# OSO-MISC-22-003_Ring_Thing.net
KiCad netlist of a schematic drawn in EAGLE
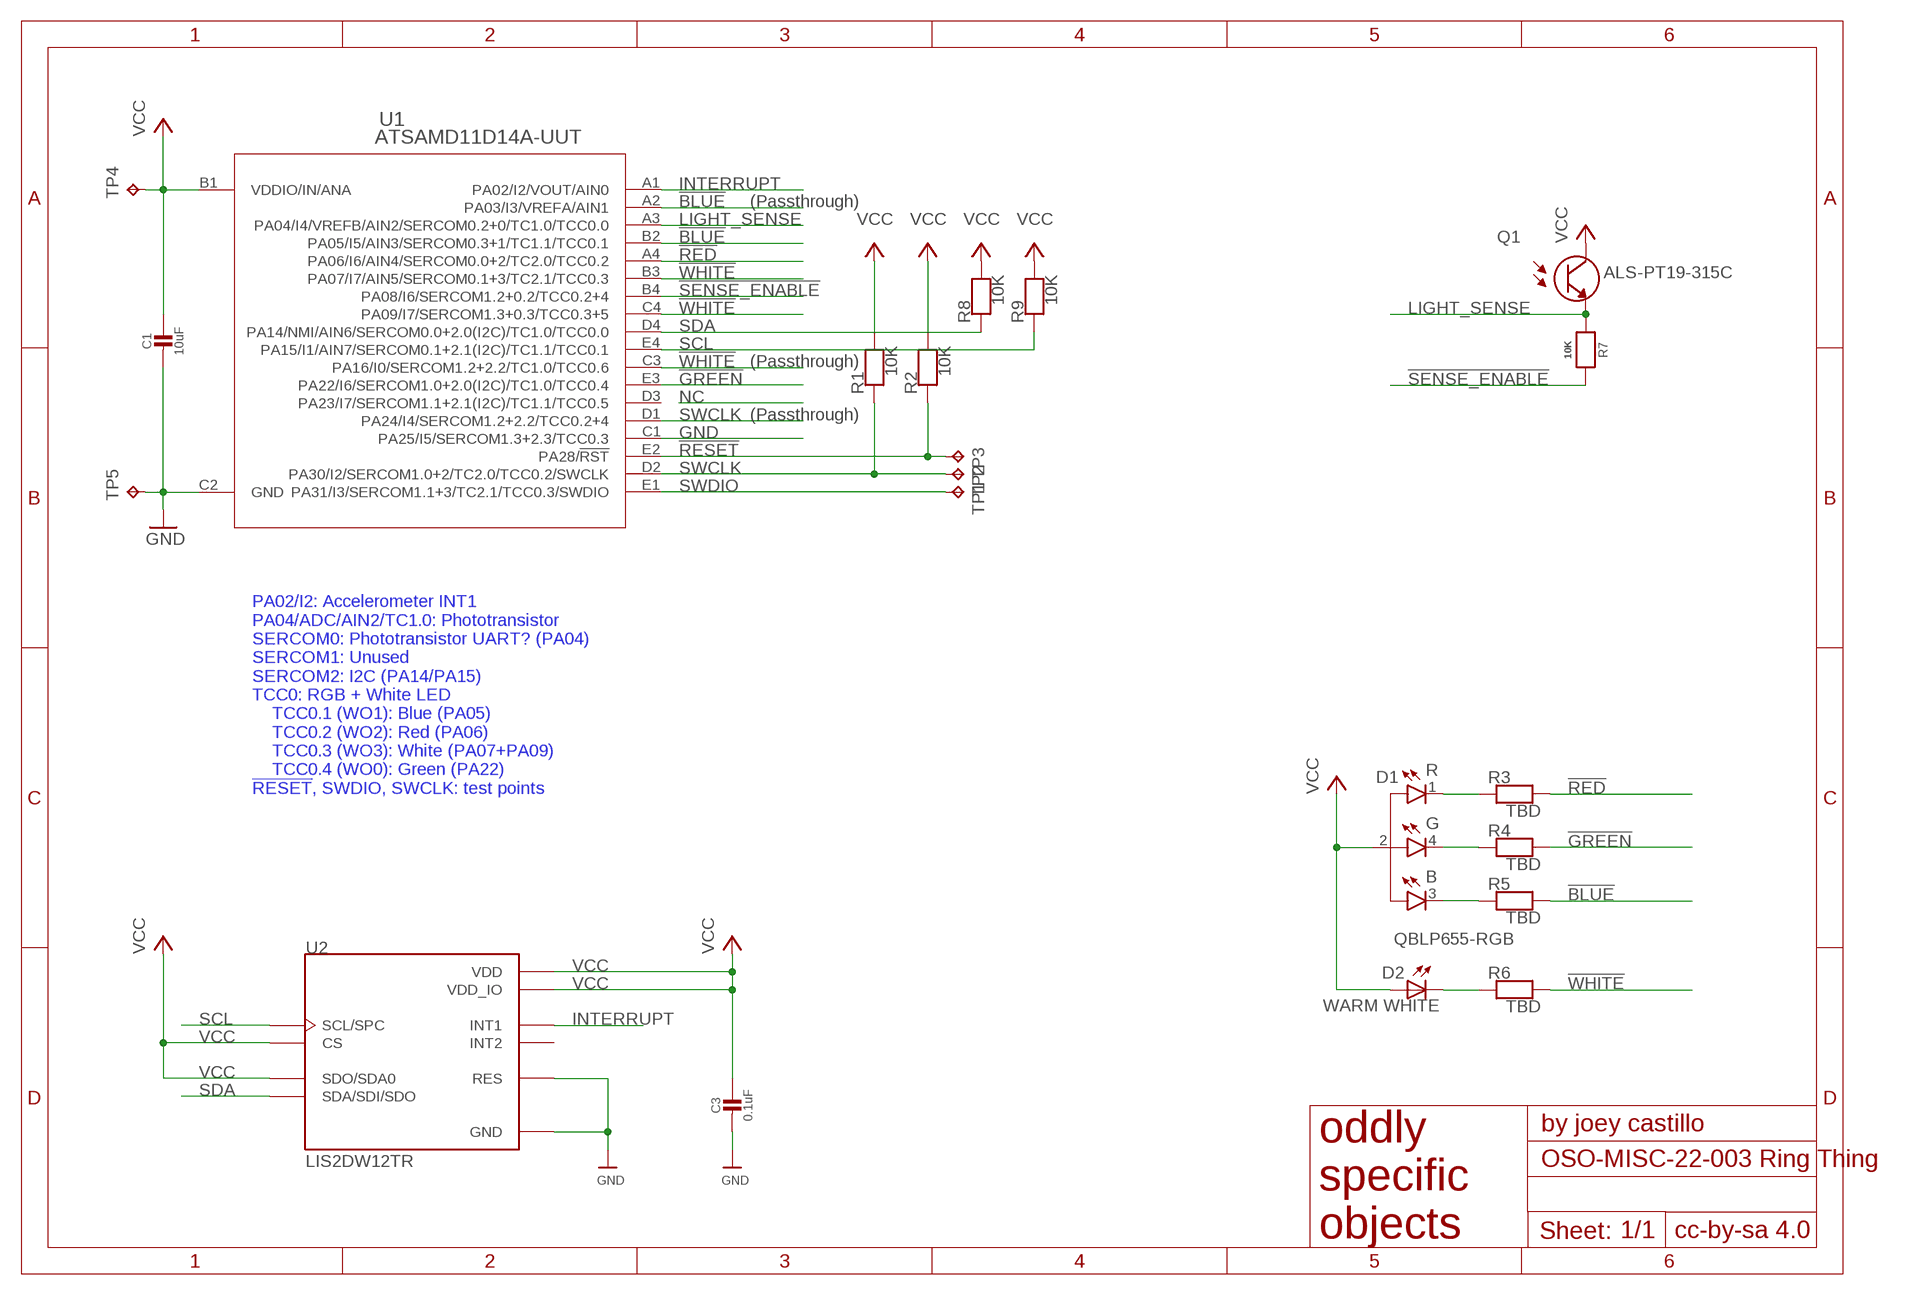
[diagram p0: schematic, sheet 1]

(export (version "E")
  (design (tool "Eeschema 10.0.6"))
  (components
    (comp (ref "C1")
      (value "10uF")
      (footprint "eagle-import:_0603MP")
      (libsource (lib "eagle-import") (part "CAP_CERAMIC_0603MP"))
    )
    (comp (ref "C3")
      (value "0.1uF")
      (footprint "eagle-import:_0402MP")
      (libsource (lib "eagle-import") (part "CAP_CERAMIC_0402MP"))
    )
    (comp (ref "D1")
      (value "QBLP655-RGB")
      (footprint "eagle-import:LED_QBLP655")
      (fields
        (field (name "DIGI-KEY_PART_NUMBER") "160-2026-1-ND")
        (field (name "MF") "Lite-On Inc.")
        (field (name "MP") "LTST-C235KGKRKT")
      )
      (libsource (lib "eagle-import") (part "QBLP655-RGB"))
    )
    (comp (ref "D2")
      (value "WARM WHITE")
      (footprint "eagle-import:CHIP-LED0603")
      (libsource (lib "eagle-import") (part "LEDCHIP-LED0603"))
    )
    (comp (ref "Q1")
      (value "ALS-PT19-315C")
      (footprint "eagle-import:XDCR_ALS-PT19-315C_L177_TR8")
      (fields
        (field (name "DIGI-KEY_PART_NUMBER") "1080-1244-2-ND")
        (field (name "MF") "Everlight")
        (field (name "MP") "ALS-PT19-315C/L177/TR8")
      )
      (libsource (lib "eagle-import") (part "ALS-PT19-315C/L177/TR8"))
    )
    (comp (ref "R1")
      (value "10K")
      (footprint "eagle-import:_0402MP")
      (libsource (lib "eagle-import") (part "RESISTOR_0402MP"))
    )
    (comp (ref "R2")
      (value "10K")
      (footprint "eagle-import:_0402MP")
      (libsource (lib "eagle-import") (part "RESISTOR_0402MP"))
    )
    (comp (ref "R3")
      (value "TBD")
      (footprint "eagle-import:_0402MP")
      (libsource (lib "eagle-import") (part "RESISTOR_0402MP"))
    )
    (comp (ref "R4")
      (value "TBD")
      (footprint "eagle-import:_0402MP")
      (libsource (lib "eagle-import") (part "RESISTOR_0402MP"))
    )
    (comp (ref "R5")
      (value "TBD")
      (footprint "eagle-import:_0402MP")
      (libsource (lib "eagle-import") (part "RESISTOR_0402MP"))
    )
    (comp (ref "R6")
      (value "TBD")
      (footprint "eagle-import:_0402MP")
      (libsource (lib "eagle-import") (part "RESISTOR_0402MP"))
    )
    (comp (ref "R7")
      (value "10K")
      (footprint "eagle-import:_0402MP")
      (libsource (lib "eagle-import") (part "RESISTOR_0402MP"))
    )
    (comp (ref "R8")
      (value "10K")
      (footprint "eagle-import:_0402MP")
      (libsource (lib "eagle-import") (part "RESISTOR_0402MP"))
    )
    (comp (ref "R9")
      (value "10K")
      (footprint "eagle-import:_0402MP")
      (libsource (lib "eagle-import") (part "RESISTOR_0402MP"))
    )
    (comp (ref "TP1")
      (value "TPTP10R")
      (footprint "eagle-import:TP10R")
      (libsource (lib "eagle-import") (part "TPTP10R"))
    )
    (comp (ref "TP2")
      (value "TPTP10R")
      (footprint "eagle-import:TP10R")
      (libsource (lib "eagle-import") (part "TPTP10R"))
    )
    (comp (ref "TP3")
      (value "TPTP10R")
      (footprint "eagle-import:TP10R")
      (libsource (lib "eagle-import") (part "TPTP10R"))
    )
    (comp (ref "TP4")
      (value "TPTP12SQ")
      (footprint "eagle-import:TP12SQ")
      (libsource (lib "eagle-import") (part "TPTP12SQ"))
    )
    (comp (ref "TP5")
      (value "TPTP20R")
      (footprint "eagle-import:TP20R")
      (libsource (lib "eagle-import") (part "TPTP20R"))
    )
    (comp (ref "U1")
      (value "ATSAMD11D14A-UUT")
      (footprint "eagle-import:WLCSP20_2P4X1P9_MCH")
      (fields (field (name "COPYRIGHT") "Copyright (C) 2022 Ultra Librarian. All rights reserved."))
      (libsource (lib "eagle-import") (part "ATSAMD11D14A-UUT"))
    )
    (comp (ref "U2")
      (value "LIS2DW12TR")
      (footprint "eagle-import:LGA12R50P4X4_200X200X70")
      (fields (field (name "MF") "STMicroelectronics"))
      (libsource (lib "eagle-import") (part "LIS2DW12TR"))
    )
  )
  (nets
    (net (code "1") (name "/INTERRUPT") (class "Default")
      (node (ref "U1") (pin "A1") (pinfunction "PA02/I2/VOUT/AIN0_A1") (pintype "bidirectional"))
      (node (ref "U2") (pin "12") (pinfunction "INT1_12") (pintype "output"))
    )
    (net (code "2") (name "/LIGHT_SENSE") (class "Default")
      (node (ref "Q1") (pin "2") (pinfunction "E_2") (pintype "passive"))
      (node (ref "R7") (pin "1") (pinfunction "1_1") (pintype "passive"))
      (node (ref "U1") (pin "A3") (pinfunction "PA04/I4/VREFB/AIN2/SERCOM0.2+0/TC1.0/TCC0.0_A3") (pintype "bidirectional"))
    )
    (net (code "4") (name "/SCL") (class "Default")
      (node (ref "R9") (pin "1") (pinfunction "1_1") (pintype "passive"))
      (node (ref "U1") (pin "E4") (pinfunction "PA15/I1/AIN7/SERCOM0.1+2.1(I2C)/TC1.1/TCC0.1_E4") (pintype "bidirectional"))
      (node (ref "U2") (pin "1") (pinfunction "SCL/SPC_1") (pintype "input"))
    )
    (net (code "5") (name "/SDA") (class "Default")
      (node (ref "R8") (pin "1") (pinfunction "1_1") (pintype "passive"))
      (node (ref "U1") (pin "D4") (pinfunction "PA14/NMI/AIN6/SERCOM0.0+2.0(I2C)/TC1.0/TCC0.0_D4") (pintype "bidirectional"))
      (node (ref "U2") (pin "4") (pinfunction "SDA/SDI/SDO_4") (pintype "bidirectional"))
    )
    (net (code "6") (name "/SWCLK") (class "Default")
      (node (ref "R1") (pin "1") (pinfunction "1_1") (pintype "passive"))
      (node (ref "TP2") (pin "TP") (pinfunction "TP_TP") (pintype "input"))
      (node (ref "U1") (pin "D1") (pinfunction "PA24/I4/SERCOM1.2+2.2/TCC0.2+4_D1") (pintype "bidirectional"))
      (node (ref "U1") (pin "D2") (pinfunction "PA30/I2/SERCOM1.0+2/TC2.0/TCC0.2/SWCLK_D2") (pintype "bidirectional"))
    )
    (net (code "7") (name "/SWDIO") (class "Default")
      (node (ref "TP1") (pin "TP") (pinfunction "TP_TP") (pintype "input"))
      (node (ref "U1") (pin "E1") (pinfunction "PA31/I3/SERCOM1.1+3/TC2.1/TCC0.3/SWDIO_E1") (pintype "bidirectional"))
    )
    (net (code "8") (name "/~{BLUE}") (class "Default")
      (node (ref "R5") (pin "2") (pinfunction "2_2") (pintype "passive"))
      (node (ref "U1") (pin "A2") (pinfunction "PA03/I3/VREFA/AIN1_A2") (pintype "bidirectional"))
      (node (ref "U1") (pin "B2") (pinfunction "PA05/I5/AIN3/SERCOM0.3+1/TC1.1/TCC0.1_B2") (pintype "bidirectional"))
    )
    (net (code "9") (name "/~{GREEN}") (class "Default")
      (node (ref "R4") (pin "2") (pinfunction "2_2") (pintype "passive"))
      (node (ref "U1") (pin "E3") (pinfunction "PA22/I6/SERCOM1.0+2.0(I2C)/TC1.0/TCC0.4_E3") (pintype "bidirectional"))
    )
    (net (code "10") (name "/~{RED}") (class "Default")
      (node (ref "R3") (pin "2") (pinfunction "2_2") (pintype "passive"))
      (node (ref "U1") (pin "A4") (pinfunction "PA06/I6/AIN4/SERCOM0.0+2/TC2.0/TCC0.2_A4") (pintype "bidirectional"))
    )
    (net (code "11") (name "/~{RESET}") (class "Default")
      (node (ref "R2") (pin "1") (pinfunction "1_1") (pintype "passive"))
      (node (ref "TP3") (pin "TP") (pinfunction "TP_TP") (pintype "input"))
      (node (ref "U1") (pin "E2") (pinfunction "PA28/~{RST}_E2") (pintype "bidirectional"))
    )
    (net (code "12") (name "/~{SENSE_ENABLE}") (class "Default")
      (node (ref "R7") (pin "2") (pinfunction "2_2") (pintype "passive"))
      (node (ref "U1") (pin "B4") (pinfunction "PA08/I6/SERCOM1.2+0.2/TCC0.2+4_B4") (pintype "bidirectional"))
    )
    (net (code "13") (name "/~{WHITE}") (class "Default")
      (node (ref "R6") (pin "2") (pinfunction "2_2") (pintype "passive"))
      (node (ref "U1") (pin "B3") (pinfunction "PA07/I7/AIN5/SERCOM0.1+3/TC2.1/TCC0.3_B3") (pintype "bidirectional"))
      (node (ref "U1") (pin "C3") (pinfunction "PA16/I0/SERCOM1.2+2.2/TC1.0/TCC0.6_C3") (pintype "bidirectional"))
      (node (ref "U1") (pin "C4") (pinfunction "PA09/I7/SERCOM1.3+0.3/TCC0.3+5_C4") (pintype "bidirectional"))
    )
    (net (code "14") (name "GND") (class "Default")
      (node (ref "C1") (pin "2") (pinfunction "2_2") (pintype "passive"))
      (node (ref "C3") (pin "2") (pinfunction "2_2") (pintype "passive"))
      (node (ref "TP5") (pin "TP") (pinfunction "TP_TP") (pintype "input"))
      (node (ref "U1") (pin "C1") (pinfunction "PA25/I5/SERCOM1.3+2.3/TCC0.3_C1") (pintype "bidirectional"))
      (node (ref "U1") (pin "C2") (pinfunction "GND_C2") (pintype "passive"))
      (node (ref "U2") (pin "6") (pinfunction "GND_6") (pintype "power_in"))
      (node (ref "U2") (pin "7") (pinfunction "RES_7") (pintype "passive"))
      (node (ref "U2") (pin "8") (pinfunction "GND_8") (pintype "power_in"))
    )
    (net (code "15") (name "Net-(D1-CB)") (class "Default")
      (node (ref "D1") (pin "3") (pinfunction "CB_3") (pintype "passive"))
      (node (ref "R5") (pin "1") (pinfunction "1_1") (pintype "passive"))
    )
    (net (code "16") (name "Net-(D1-CG)") (class "Default")
      (node (ref "D1") (pin "4") (pinfunction "CG_4") (pintype "passive"))
      (node (ref "R4") (pin "1") (pinfunction "1_1") (pintype "passive"))
    )
    (net (code "17") (name "Net-(D1-CR)") (class "Default")
      (node (ref "D1") (pin "1") (pinfunction "CR_1") (pintype "passive"))
      (node (ref "R3") (pin "1") (pinfunction "1_1") (pintype "passive"))
    )
    (net (code "18") (name "Net-(D2-PadC)") (class "Default")
      (node (ref "D2") (pin "C") (pinfunction "C_C") (pintype "passive"))
      (node (ref "R6") (pin "1") (pinfunction "1_1") (pintype "passive"))
    )
    (net (code "19") (name "VCC") (class "Default")
      (node (ref "C1") (pin "1") (pinfunction "1_1") (pintype "passive"))
      (node (ref "C3") (pin "1") (pinfunction "1_1") (pintype "passive"))
      (node (ref "D1") (pin "2") (pinfunction "A_2") (pintype "passive"))
      (node (ref "D2") (pin "A") (pinfunction "A_A") (pintype "passive"))
      (node (ref "Q1") (pin "1") (pinfunction "C_1") (pintype "passive"))
      (node (ref "R1") (pin "2") (pinfunction "2_2") (pintype "passive"))
      (node (ref "R2") (pin "2") (pinfunction "2_2") (pintype "passive"))
      (node (ref "R8") (pin "2") (pinfunction "2_2") (pintype "passive"))
      (node (ref "R9") (pin "2") (pinfunction "2_2") (pintype "passive"))
      (node (ref "TP4") (pin "TP") (pinfunction "TP_TP") (pintype "input"))
      (node (ref "U1") (pin "B1") (pinfunction "VDDIO/IN/ANA_B1") (pintype "power_in"))
      (node (ref "U2") (pin "10") (pinfunction "VDD_IO_10") (pintype "power_in"))
      (node (ref "U2") (pin "2") (pinfunction "CS_2") (pintype "input"))
      (node (ref "U2") (pin "3") (pinfunction "SDO/SDA0_3") (pintype "bidirectional"))
      (node (ref "U2") (pin "9") (pinfunction "VDD_9") (pintype "power_in"))
    )
    (net (code "20") (name "unconnected-(U1-PA23{slash}I7{slash}SERCOM1.1+2.1(I2C){slash}TC1.1{slash}TCC0.5-PadD3)") (class "Default")
      (node (ref "U1") (pin "D3") (pinfunction "PA23/I7/SERCOM1.1+2.1(I2C)/TC1.1/TCC0.5_D3") (pintype "bidirectional"))
    )
    (net (code "21") (name "unconnected-(U2-INT2-Pad11)") (class "Default")
      (node (ref "U2") (pin "11") (pinfunction "INT2_11") (pintype "output"))
    )
  )
)
